# IMU.net
KiCad netlist of a schematic drawn in Altium Designer
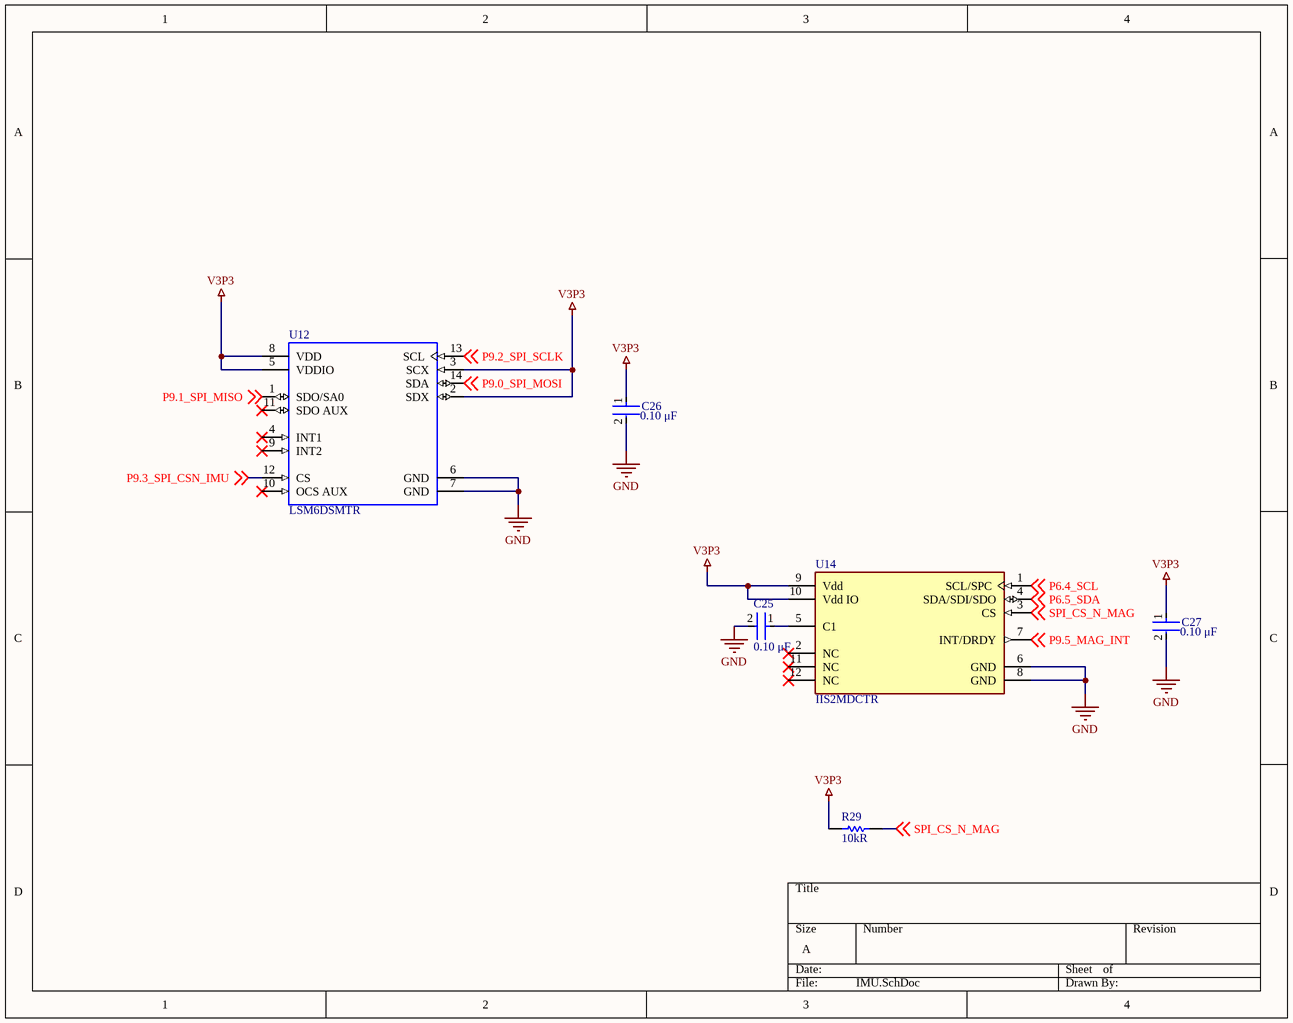
[diagram p0: IMU.SchDoc]

(export (version "E")
  (design (tool "Eeschema 10.0.6"))
  (components
    (comp (ref "C25")
      (value "C0805C104K5RACTU")
      (footprint "FP-C0805C-DN-MFG")
      (description "CAP CER 0.1UF 50V X7R 0805")
      (fields
        (field (name "MANUFACTURER") "KEMET")
        (field (name "OCTOPART") "https://octopart.com/c0805c104k5ractu-kemet-143926")
        (field (name "CAPACITANCE") "0.10 μF")
      )
      (libsource (lib "Altium Content Vault") (part "b4654b650e69147ec39a6b967a45e02"))
    )
    (comp (ref "C26")
      (value "C0805C104K5RACTU")
      (footprint "FP-C0805C-DN-MFG")
      (description "CAP CER 0.1UF 50V X7R 0805")
      (fields
        (field (name "MANUFACTURER") "KEMET")
        (field (name "OCTOPART") "https://octopart.com/c0805c104k5ractu-kemet-143926")
        (field (name "CAPACITANCE") "0.10 μF")
      )
      (libsource (lib "Altium Content Vault") (part "b4654b650e69147ec39a6b967a45e02"))
    )
    (comp (ref "C27")
      (value "C0805C104K5RACTU")
      (footprint "FP-C0805C-DN-MFG")
      (description "CAP CER 0.1UF 50V X7R 0805")
      (fields
        (field (name "MANUFACTURER") "KEMET")
        (field (name "OCTOPART") "https://octopart.com/c0805c104k5ractu-kemet-143926")
        (field (name "CAPACITANCE") "0.10 μF")
      )
      (libsource (lib "Altium Content Vault") (part "b4654b650e69147ec39a6b967a45e02"))
    )
    (comp (ref "R29")
      (value "RC0805FR-0710KL")
      (footprint "RESC2013X60X35NL10T20")
      (description "Chip Resistor, 10 KOhm, +/- 1%, 0.125 W, -55 to 155 degC, 0805 (2012 Metric), RoHS, Tape and Reel")
      (fields
        (field (name "MANUFACTURER") "Yageo")
        (field (name "RESISTANCE") "10kR")
        (field (name "TOLERANCE") "1%")
      )
      (libsource (lib "Altium Content Vault") (part "RES-2"))
    )
    (comp (ref "U12")
      (value "LSM6DSMTR")
      (footprint "LSM6DSMTR")
      (description "Analog Circuit, 1 Func, CMOS, PBGA14")
      (fields
        (field (name "OCTOPART") "https://octopart.com/lsm6dsmtr-stmicroelectronics-66358194")
        (field (name "MANUFACTURER") "STMicroelectronics")
      )
      (libsource (lib "uw-madison-parts") (part "IC-LSM6DSMTR"))
    )
    (comp (ref "U14")
      (value "IIS2MDCTR")
      (footprint "FP-LGA-12-DM00170568-MFG")
      (description "SENSOR MR I2C/SPI 12LGA")
      (libsource (lib "Components - 01.10.25 - 15.10") (part "CMP-12173-000003-1"))
    )
  )
  (nets
    (net (code "1") (name "GND") (class "Default")
      (node (ref "C25") (pin "2") (pinfunction "2_2") (pintype "passive"))
      (node (ref "C26") (pin "2") (pinfunction "2_2") (pintype "passive"))
      (node (ref "C27") (pin "2") (pinfunction "2_2") (pintype "passive"))
      (node (ref "U12") (pin "6") (pinfunction "GND_6") (pintype "power_in"))
      (node (ref "U12") (pin "7") (pinfunction "GND_7") (pintype "power_in"))
      (node (ref "U14") (pin "6") (pinfunction "GND_6") (pintype "power_in"))
      (node (ref "U14") (pin "8") (pinfunction "GND_8") (pintype "power_in"))
    )
    (net (code "2") (name "Net-(U14-C1)") (class "Default")
      (node (ref "C25") (pin "1") (pinfunction "1_1") (pintype "passive"))
      (node (ref "U14") (pin "5") (pinfunction "C1_5") (pintype "passive"))
    )
    (net (code "3") (name "P6.4_SCL") (class "Default")
      (node (ref "U14") (pin "1") (pinfunction "SCL/SPC_1") (pintype "input"))
    )
    (net (code "4") (name "P6.5_SDA") (class "Default")
      (node (ref "U14") (pin "4") (pinfunction "SDA/SDI/SDO_4") (pintype "bidirectional"))
    )
    (net (code "5") (name "P9.0_SPI_MOSI") (class "Default")
      (node (ref "U12") (pin "14") (pinfunction "SDA_14") (pintype "bidirectional"))
    )
    (net (code "6") (name "P9.1_SPI_MISO") (class "Default")
      (node (ref "U12") (pin "1") (pinfunction "SDO/SA0_1") (pintype "bidirectional"))
    )
    (net (code "7") (name "P9.2_SPI_SCLK") (class "Default")
      (node (ref "U12") (pin "13") (pinfunction "SCL_13") (pintype "input"))
    )
    (net (code "8") (name "P9.3_SPI_CSN_IMU") (class "Default")
      (node (ref "U12") (pin "12") (pinfunction "CS_12") (pintype "input"))
    )
    (net (code "9") (name "P9.5_MAG_INT") (class "Default")
      (node (ref "U14") (pin "7") (pinfunction "INT/DRDY_7") (pintype "output"))
    )
    (net (code "10") (name "SPI_CS_N_MAG") (class "Default")
      (node (ref "R29") (pin "2") (pinfunction "2_2") (pintype "passive"))
      (node (ref "U14") (pin "3") (pinfunction "CS_3") (pintype "input"))
    )
    (net (code "11") (name "V3P3") (class "Default")
      (node (ref "C26") (pin "1") (pinfunction "1_1") (pintype "passive"))
      (node (ref "C27") (pin "1") (pinfunction "1_1") (pintype "passive"))
      (node (ref "R29") (pin "1") (pinfunction "1_1") (pintype "passive"))
      (node (ref "U12") (pin "2") (pinfunction "SDX_2") (pintype "bidirectional"))
      (node (ref "U12") (pin "3") (pinfunction "SCX_3") (pintype "input"))
      (node (ref "U12") (pin "5") (pinfunction "VDDIO_5") (pintype "power_in"))
      (node (ref "U12") (pin "8") (pinfunction "VDD_8") (pintype "power_in"))
      (node (ref "U14") (pin "10") (pinfunction "Vdd_IO_10") (pintype "power_in"))
      (node (ref "U14") (pin "9") (pinfunction "Vdd_9") (pintype "power_in"))
    )
    (net (code "12") (name "unconnected-(U12-INT1-Pad4)") (class "Default")
      (node (ref "U12") (pin "4") (pinfunction "INT1_4") (pintype "input+no_connect"))
    )
    (net (code "13") (name "unconnected-(U12-INT2-Pad9)") (class "Default")
      (node (ref "U12") (pin "9") (pinfunction "INT2_9") (pintype "input+no_connect"))
    )
    (net (code "14") (name "unconnected-(U12-OCS_AUX-Pad10)") (class "Default")
      (node (ref "U12") (pin "10") (pinfunction "OCS_AUX_10") (pintype "input+no_connect"))
    )
    (net (code "15") (name "unconnected-(U12-SDO_AUX-Pad11)") (class "Default")
      (node (ref "U12") (pin "11") (pinfunction "SDO_AUX_11") (pintype "bidirectional+no_connect"))
    )
    (net (code "16") (name "unconnected-(U14-NC-Pad2)") (class "Default")
      (node (ref "U14") (pin "2") (pinfunction "NC_2") (pintype "passive+no_connect"))
    )
    (net (code "17") (name "unconnected-(U14-NC-Pad11)") (class "Default")
      (node (ref "U14") (pin "11") (pinfunction "NC_11") (pintype "passive+no_connect"))
    )
    (net (code "18") (name "unconnected-(U14-NC-Pad12)") (class "Default")
      (node (ref "U14") (pin "12") (pinfunction "NC_12") (pintype "passive+no_connect"))
    )
  )
)
